# AtoD_Conversion.net
KiCad netlist of a schematic drawn in Altium Designer
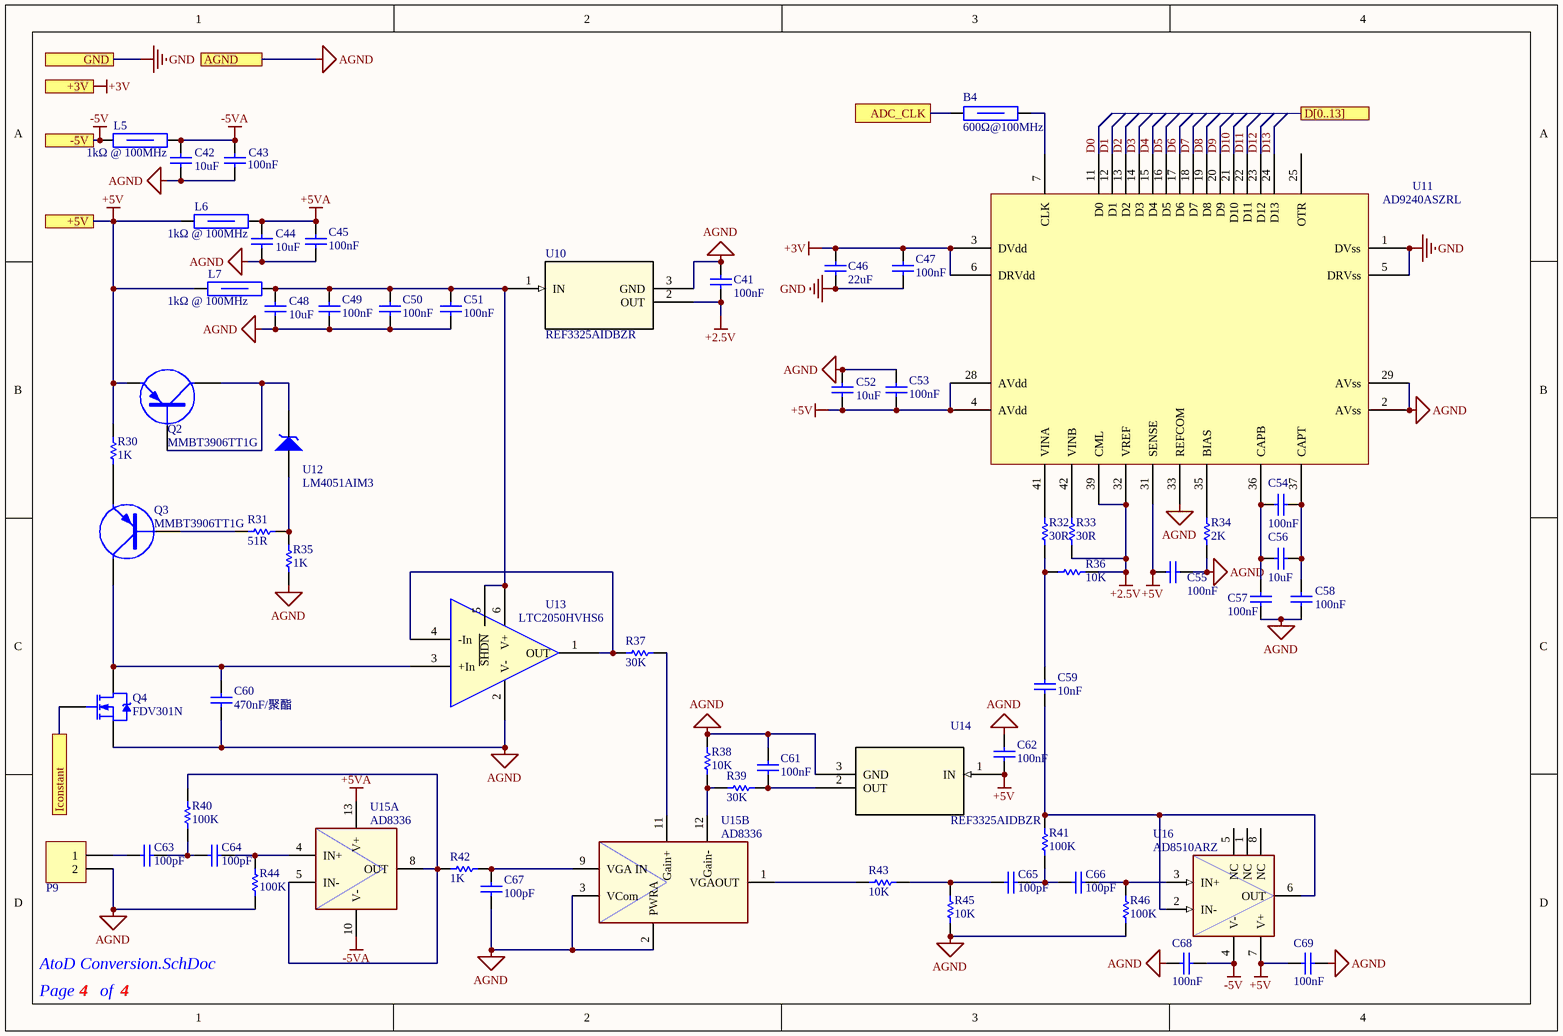
[diagram p0: AtoD Conversion.SchDoc]

(export (version "E")
  (design (tool "Eeschema 10.0.6"))
  (components
    (comp (ref "B4")
      (value "600Ω@100MHz")
      (footprint "R0805_L")
      (description "600Ω @ 100MHz \r\n线路数 1 \r\n额定电流（最大） 600mA \r\n直流电阻（DCR）（最大） 210mΩ")
      (libsource (lib "00Lib") (part "600Ω@100MHz"))
    )
    (comp (ref "C41")
      (value "100nF")
      (footprint "R0603_C")
      (description "精度 ±10% \r\n容值 100nF \r\n额定电压 50V \r\n温漂系数（介质材料) X7R")
      (libsource (lib "00Lib") (part "100nF/0603/50V"))
    )
    (comp (ref "C42")
      (value "10uF")
      (footprint "R0805_C")
      (description "精度 ±10% \r\n容值 10uF \r\n额定电压 16V \r\n温漂系数（介质材料) X7R")
      (libsource (lib "00Lib") (part "10uF/0805/16V"))
    )
    (comp (ref "C43")
      (value "100nF")
      (footprint "R0603_C")
      (description "精度 ±10% \r\n容值 100nF \r\n额定电压 50V \r\n温漂系数（介质材料) X7R")
      (libsource (lib "00Lib") (part "100nF/0603/50V"))
    )
    (comp (ref "C44")
      (value "10uF")
      (footprint "R0805_C")
      (description "精度 ±10% \r\n容值 10uF \r\n额定电压 16V \r\n温漂系数（介质材料) X7R")
      (libsource (lib "00Lib") (part "10uF/0805/16V"))
    )
    (comp (ref "C45")
      (value "100nF")
      (footprint "R0603_C")
      (description "精度 ±10% \r\n容值 100nF \r\n额定电压 50V \r\n温漂系数（介质材料) X7R")
      (libsource (lib "00Lib") (part "100nF/0603/50V"))
    )
    (comp (ref "C46")
      (value "22uF")
      (footprint "R0805_C")
      (description "精度 ±20% \r\n容值 22uF \r\n额定电压 25V \r\n温漂系数（介质材料) X5R")
      (libsource (lib "C") (part "22uF/0805/25V"))
    )
    (comp (ref "C47")
      (value "100nF")
      (footprint "R0603_C")
      (description "精度 ±10% \r\n容值 100nF \r\n额定电压 50V \r\n温漂系数（介质材料) X7R")
      (libsource (lib "00Lib") (part "100nF/0603/50V"))
    )
    (comp (ref "C48")
      (value "10uF")
      (footprint "R0805_C")
      (description "精度 ±10% \r\n容值 10uF \r\n额定电压 16V \r\n温漂系数（介质材料) X7R")
      (libsource (lib "00Lib") (part "10uF/0805/16V"))
    )
    (comp (ref "C49")
      (value "100nF")
      (footprint "R0603_C")
      (description "精度 ±10% \r\n容值 100nF \r\n额定电压 50V \r\n温漂系数（介质材料) X7R")
      (libsource (lib "00Lib") (part "100nF/0603/50V"))
    )
    (comp (ref "C50")
      (value "100nF")
      (footprint "R0603_C")
      (description "精度 ±10% \r\n容值 100nF \r\n额定电压 50V \r\n温漂系数（介质材料) X7R")
      (libsource (lib "00Lib") (part "100nF/0603/50V"))
    )
    (comp (ref "C51")
      (value "100nF")
      (footprint "R0603_C")
      (description "精度 ±10% \r\n容值 100nF \r\n额定电压 50V \r\n温漂系数（介质材料) X7R")
      (libsource (lib "00Lib") (part "100nF/0603/50V"))
    )
    (comp (ref "C52")
      (value "10uF")
      (footprint "R0805_C")
      (description "精度 ±10% \r\n容值 10uF \r\n额定电压 16V \r\n温漂系数（介质材料) X7R")
      (libsource (lib "00Lib") (part "10uF/0805/16V"))
    )
    (comp (ref "C53")
      (value "100nF")
      (footprint "R0603_C")
      (description "精度 ±10% \r\n容值 100nF \r\n额定电压 50V \r\n温漂系数（介质材料) X7R")
      (libsource (lib "00Lib") (part "100nF/0603/50V"))
    )
    (comp (ref "C54")
      (value "100nF")
      (footprint "R0603_C")
      (description "精度 ±10% \r\n容值 100nF \r\n额定电压 50V \r\n温漂系数（介质材料) X7R")
      (libsource (lib "00Lib") (part "100nF/0603/50V"))
    )
    (comp (ref "C55")
      (value "100nF")
      (footprint "R0603_C")
      (description "精度 ±10% \r\n容值 100nF \r\n额定电压 50V \r\n温漂系数（介质材料) X7R")
      (libsource (lib "00Lib") (part "100nF/0603/50V"))
    )
    (comp (ref "C56")
      (value "10uF")
      (footprint "R0805_C")
      (description "精度 ±10% \r\n容值 10uF \r\n额定电压 16V \r\n温漂系数（介质材料) X7R")
      (libsource (lib "00Lib") (part "10uF/0805/16V"))
    )
    (comp (ref "C57")
      (value "100nF")
      (footprint "R0603_C")
      (description "精度 ±10% \r\n容值 100nF \r\n额定电压 50V \r\n温漂系数（介质材料) X7R")
      (libsource (lib "00Lib") (part "100nF/0603/50V"))
    )
    (comp (ref "C58")
      (value "100nF")
      (footprint "R0603_C")
      (description "精度 ±10% \r\n容值 100nF \r\n额定电压 50V \r\n温漂系数（介质材料) X7R")
      (libsource (lib "00Lib") (part "100nF/0603/50V"))
    )
    (comp (ref "C59")
      (value "10nF")
      (footprint "R0603_C")
      (description "精度 ±5% \r\n容值 10nF \r\n额定电压 50V \r\n温漂系数（介质材料) C0G")
      (libsource (lib "00Lib") (part "10nF/0603/C0G/50V"))
    )
    (comp (ref "C60")
      (value "470nF/聚酯")
      (footprint "P=10MM -L")
      (description "聚酯薄膜电容 \r\n脚间距（mm） 10 \r\n精度 ±5% \r\n容值 470nF \r\n额定直流耐压DC 450V \r\n工作温度 -55℃ ~ +105℃")
      (libsource (lib "00Lib") (part "470nF/10mm/450V"))
    )
    (comp (ref "C61")
      (value "100nF")
      (footprint "R0603_C")
      (description "精度 ±10% \r\n容值 100nF \r\n额定电压 50V \r\n温漂系数（介质材料) X7R")
      (libsource (lib "00Lib") (part "100nF/0603/50V"))
    )
    (comp (ref "C62")
      (value "100nF")
      (footprint "R0603_C")
      (description "精度 ±10% \r\n容值 100nF \r\n额定电压 50V \r\n温漂系数（介质材料) X7R")
      (libsource (lib "00Lib") (part "100nF/0603/50V"))
    )
    (comp (ref "C63")
      (value "100pF")
      (footprint "R0603_C")
      (description "精度 ±5% \r\n容值 100pF \r\n额定电压 50V \r\n温漂系数（介质材料) C0G")
      (libsource (lib "00Lib") (part "100pF/0603/50V"))
    )
    (comp (ref "C64")
      (value "100pF")
      (footprint "R0603_C")
      (description "精度 ±5% \r\n容值 100pF \r\n额定电压 50V \r\n温漂系数（介质材料) C0G")
      (libsource (lib "00Lib") (part "100pF/0603/50V"))
    )
    (comp (ref "C65")
      (value "100pF")
      (footprint "R0603_C")
      (description "精度 ±5% \r\n容值 100pF \r\n额定电压 50V \r\n温漂系数（介质材料) C0G")
      (libsource (lib "00Lib") (part "100pF/0603/50V"))
    )
    (comp (ref "C66")
      (value "100pF")
      (footprint "R0603_C")
      (description "精度 ±5% \r\n容值 100pF \r\n额定电压 50V \r\n温漂系数（介质材料) C0G")
      (libsource (lib "00Lib") (part "100pF/0603/50V"))
    )
    (comp (ref "C67")
      (value "100pF")
      (footprint "R0603_C")
      (description "精度 ±5% \r\n容值 100pF \r\n额定电压 50V \r\n温漂系数（介质材料) C0G")
      (libsource (lib "00Lib") (part "100pF/0603/50V"))
    )
    (comp (ref "C68")
      (value "100nF")
      (footprint "R0603_C")
      (description "精度 ±10% \r\n容值 100nF \r\n额定电压 50V \r\n温漂系数（介质材料) X7R")
      (libsource (lib "00Lib") (part "100nF/0603/50V"))
    )
    (comp (ref "C69")
      (value "100nF")
      (footprint "R0603_C")
      (description "精度 ±10% \r\n容值 100nF \r\n额定电压 50V \r\n温漂系数（介质材料) X7R")
      (libsource (lib "00Lib") (part "100nF/0603/50V"))
    )
    (comp (ref "L5")
      (value "1kΩ @ 100MHz")
      (footprint "R1206_L")
      (description "阻抗 @ 频率 1kΩ @ 100MHz \r\n线路数 1 \r\n额定电流（最大） 2A \r\n直流电阻（DCR）（最大） 120mΩ")
      (libsource (lib "00Lib") (part "1kΩ@100MHz"))
    )
    (comp (ref "L6")
      (value "1kΩ @ 100MHz")
      (footprint "R1206_L")
      (description "阻抗 @ 频率 1kΩ @ 100MHz \r\n线路数 1 \r\n额定电流（最大） 2A \r\n直流电阻（DCR）（最大） 120mΩ")
      (libsource (lib "00Lib") (part "1kΩ@100MHz"))
    )
    (comp (ref "L7")
      (value "1kΩ @ 100MHz")
      (footprint "R1206_L")
      (description "阻抗 @ 频率 1kΩ @ 100MHz \r\n线路数 1 \r\n额定电流（最大） 2A \r\n直流电阻（DCR）（最大） 120mΩ")
      (libsource (lib "00Lib") (part "1kΩ@100MHz"))
    )
    (comp (ref "P9")
      (value "Header 2")
      (footprint "CP1X2")
      (description "Header, 2-Pin")
      (libsource (lib "00Lib") (part "Header 2"))
    )
    (comp (ref "Q2")
      (value "MMBT3906TT1G")
      (footprint "SOT-23(SOT-23-3)")
      (description "额定功率 200mW \r\n集电极电流Ic 200mA \r\n集射极击穿电压Vce 40V \r\n晶体管类型 PNP")
      (libsource (lib "00Lib") (part "MMBT3906TT1G"))
    )
    (comp (ref "Q3")
      (value "MMBT3906TT1G")
      (footprint "SOT-23(SOT-23-3)")
      (description "额定功率 200mW \r\n集电极电流Ic 200mA \r\n集射极击穿电压Vce 40V \r\n晶体管类型 PNP")
      (libsource (lib "00Lib") (part "MMBT3906TT1G"))
    )
    (comp (ref "Q4") (value "FDV301N") (footprint "SOT-23") (libsource (lib "00Lib") (part "FDV301N")))
    (comp (ref "R30")
      (value "1K")
      (footprint "R0603_R")
      (description "精度 ±1% \r\n温度系数 ±100ppm/℃ \r\n阻值 1kΩ \r\n功率 0.1W")
      (libsource (lib "00Lib") (part "1K/0603"))
    )
    (comp (ref "R31")
      (value "51R")
      (footprint "R0603_R")
      (description "精度 ±1% \r\n温度系数 ±100ppm/℃ \r\n功率 0.1W \r\n阻值 51Ω")
      (libsource (lib "00Lib") (part "51R/0603"))
    )
    (comp (ref "R32")
      (value "30R")
      (footprint "R0603_R")
      (description "精度 ±1% \r\n阻值 30Ω \r\n温度系数 ±100ppm/℃ \r\n功率 0.1W")
      (libsource (lib "00Lib") (part "30R/0603"))
    )
    (comp (ref "R33")
      (value "30R")
      (footprint "R0603_R")
      (description "精度 ±1% \r\n阻值 30Ω \r\n温度系数 ±100ppm/℃ \r\n功率 0.1W")
      (libsource (lib "00Lib") (part "30R/0603"))
    )
    (comp (ref "R34")
      (value "2K")
      (footprint "R0603_R")
      (description "精度 ±1% \r\n阻值 2kΩ \r\n温度系数 ±100ppm/℃ \r\n功率 0.1W")
      (libsource (lib "00Lib") (part "2K/0603"))
    )
    (comp (ref "R35")
      (value "1K")
      (footprint "R0603_R")
      (description "精度 ±1% \r\n温度系数 ±100ppm/℃ \r\n阻值 1kΩ \r\n功率 0.1W")
      (libsource (lib "00Lib") (part "1K/0603"))
    )
    (comp (ref "R36")
      (value "10K")
      (footprint "R0603_R")
      (description "精度 ±1% \r\n温度系数 ±100ppm/℃ \r\n阻值 10kΩ \r\n功率 0.1W")
      (libsource (lib "00Lib") (part "10K/0603"))
    )
    (comp (ref "R37")
      (value "30K")
      (footprint "R0603_R")
      (description "精度 ±1% \r\n阻值 30kΩ \r\n温度系数 ±100ppm/℃ \r\n功率 0.1W")
      (libsource (lib "00Lib") (part "30K/0603"))
    )
    (comp (ref "R38")
      (value "10K")
      (footprint "R0603_R")
      (description "精度 ±1% \r\n温度系数 ±100ppm/℃ \r\n阻值 10kΩ \r\n功率 0.1W")
      (libsource (lib "00Lib") (part "10K/0603"))
    )
    (comp (ref "R39")
      (value "30K")
      (footprint "R0603_R")
      (description "精度 ±1% \r\n阻值 30kΩ \r\n温度系数 ±100ppm/℃ \r\n功率 0.1W")
      (libsource (lib "00Lib") (part "30K/0603"))
    )
    (comp (ref "R40")
      (value "100K")
      (footprint "R0603_R")
      (description "精度 ±1% \r\n阻值 100kΩ \r\n温度系数 ±100ppm/℃ \r\n功率 0.1W")
      (libsource (lib "00Lib") (part "100K/0603"))
    )
    (comp (ref "R41")
      (value "100K")
      (footprint "R0603_R")
      (description "精度 ±1% \r\n阻值 100kΩ \r\n温度系数 ±100ppm/℃ \r\n功率 0.1W")
      (libsource (lib "00Lib") (part "100K/0603"))
    )
    (comp (ref "R42")
      (value "1K")
      (footprint "R0603_R")
      (description "精度 ±1% \r\n温度系数 ±100ppm/℃ \r\n阻值 1kΩ \r\n功率 0.1W")
      (libsource (lib "00Lib") (part "1K/0603"))
    )
    (comp (ref "R43")
      (value "10K")
      (footprint "R0603_R")
      (description "精度 ±1% \r\n温度系数 ±100ppm/℃ \r\n阻值 10kΩ \r\n功率 0.1W")
      (libsource (lib "00Lib") (part "10K/0603"))
    )
    (comp (ref "R44")
      (value "100K")
      (footprint "R0603_R")
      (description "精度 ±1% \r\n阻值 100kΩ \r\n温度系数 ±100ppm/℃ \r\n功率 0.1W")
      (libsource (lib "00Lib") (part "100K/0603"))
    )
    (comp (ref "R45")
      (value "10K")
      (footprint "R0603_R")
      (description "精度 ±1% \r\n温度系数 ±100ppm/℃ \r\n阻值 10kΩ \r\n功率 0.1W")
      (libsource (lib "00Lib") (part "10K/0603"))
    )
    (comp (ref "R46")
      (value "100K")
      (footprint "R0603_R")
      (description "精度 ±1% \r\n阻值 100kΩ \r\n温度系数 ±100ppm/℃ \r\n功率 0.1W")
      (libsource (lib "00Lib") (part "100K/0603"))
    )
    (comp (ref "U10")
      (value "REF3325AIDBZR")
      (footprint "SOT-23(SOT-23-3)")
      (libsource (lib "00Lib") (part "REF3325AIDBZR"))
    )
    (comp (ref "U11")
      (value "AD9240ASZRL")
      (footprint "MQFP44")
      (libsource (lib "00Lib") (part "AD9240ASZRL"))
    )
    (comp (ref "U12")
      (value "LM4051AIM3")
      (footprint "SOT-23(SOT-23-3)")
      (libsource (lib "00Lib") (part "LM4051AIM3-ADJ/NOPB"))
    )
    (comp (ref "U13")
      (value "LTC2050HVHS6")
      (footprint "DBV0006A_N")
      (libsource (lib "00Lib") (part "LTC2050HVHS6"))
    )
    (comp (ref "U14")
      (value "REF3325AIDBZR")
      (footprint "SOT-23(SOT-23-3)")
      (libsource (lib "") (part "REF3325AIDBZR_1"))
    )
    (comp (ref "U15") (value "AD8336") (footprint "LFCSP16") (libsource (lib "00Lib") (part "AD8336ACPZ WP")))
    (comp (ref "U16")
      (value "AD8510ARZ")
      (footprint "SOP-8_150mil")
      (libsource (lib "00Lib") (part "AD8510ARZ"))
    )
  )
  (nets
    (net (code "1") (name "+2.5V") (class "Default")
      (node (ref "C41") (pin "2") (pinfunction "2_2") (pintype "passive"))
      (node (ref "R33") (pin "1") (pinfunction "1_1") (pintype "passive"))
      (node (ref "R36") (pin "1") (pinfunction "1_1") (pintype "passive"))
      (node (ref "U10") (pin "2") (pinfunction "OUT_2") (pintype "power_in"))
      (node (ref "U11") (pin "32") (pinfunction "VREF_32") (pintype "passive"))
      (node (ref "U11") (pin "39") (pinfunction "CML_39") (pintype "passive"))
    )
    (net (code "2") (name "+3V") (class "Default")
      (node (ref "C46") (pin "2") (pinfunction "2_2") (pintype "passive"))
      (node (ref "C47") (pin "2") (pinfunction "2_2") (pintype "passive"))
      (node (ref "U11") (pin "3") (pinfunction "DVdd_3") (pintype "passive"))
      (node (ref "U11") (pin "6") (pinfunction "DRVdd_6") (pintype "passive"))
    )
    (net (code "3") (name "+5V") (class "Default")
      (node (ref "C52") (pin "1") (pinfunction "1_1") (pintype "passive"))
      (node (ref "C53") (pin "1") (pinfunction "1_1") (pintype "passive"))
      (node (ref "C55") (pin "2") (pinfunction "2_2") (pintype "passive"))
      (node (ref "C62") (pin "1") (pinfunction "1_1") (pintype "passive"))
      (node (ref "C69") (pin "2") (pinfunction "2_2") (pintype "passive"))
      (node (ref "L6") (pin "1") (pinfunction "1_1") (pintype "passive"))
      (node (ref "L7") (pin "1") (pinfunction "1_1") (pintype "passive"))
      (node (ref "Q2") (pin "2") (pinfunction "E_2") (pintype "passive"))
      (node (ref "R30") (pin "2") (pinfunction "2_2") (pintype "passive"))
      (node (ref "U11") (pin "28") (pinfunction "AVdd_28") (pintype "passive"))
      (node (ref "U11") (pin "31") (pinfunction "SENSE_31") (pintype "passive"))
      (node (ref "U11") (pin "4") (pinfunction "AVdd_4") (pintype "passive"))
      (node (ref "U14") (pin "1") (pinfunction "IN_1") (pintype "input"))
      (node (ref "U16") (pin "7") (pinfunction "V+_7") (pintype "passive"))
    )
    (net (code "4") (name "+5VA") (class "Default")
      (node (ref "C44") (pin "2") (pinfunction "2_2") (pintype "passive"))
      (node (ref "C45") (pin "2") (pinfunction "2_2") (pintype "passive"))
      (node (ref "L6") (pin "2") (pinfunction "2_2") (pintype "passive"))
      (node (ref "U15") (pin "13") (pinfunction "V+_13") (pintype "passive"))
    )
    (net (code "5") (name "-5V") (class "Default")
      (node (ref "C68") (pin "1") (pinfunction "1_1") (pintype "passive"))
      (node (ref "L5") (pin "1") (pinfunction "1_1") (pintype "passive"))
      (node (ref "U16") (pin "4") (pinfunction "V-_4") (pintype "power_in"))
    )
    (net (code "6") (name "-5VA") (class "Default")
      (node (ref "C42") (pin "2") (pinfunction "2_2") (pintype "passive"))
      (node (ref "C43") (pin "2") (pinfunction "2_2") (pintype "passive"))
      (node (ref "L5") (pin "2") (pinfunction "2_2") (pintype "passive"))
      (node (ref "U15") (pin "10") (pinfunction "V-_10") (pintype "passive"))
    )
    (net (code "7") (name "/ADC_CLK") (class "Default")
      (node (ref "B4") (pin "1") (pinfunction "1_1") (pintype "passive"))
    )
    (net (code "8") (name "/D0") (class "Default")
      (node (ref "U11") (pin "11") (pinfunction "D0_11") (pintype "passive"))
    )
    (net (code "9") (name "/D1") (class "Default")
      (node (ref "U11") (pin "12") (pinfunction "D1_12") (pintype "passive"))
    )
    (net (code "10") (name "/D2") (class "Default")
      (node (ref "U11") (pin "13") (pinfunction "D2_13") (pintype "passive"))
    )
    (net (code "11") (name "/D3") (class "Default")
      (node (ref "U11") (pin "14") (pinfunction "D3_14") (pintype "passive"))
    )
    (net (code "12") (name "/D4") (class "Default")
      (node (ref "U11") (pin "15") (pinfunction "D4_15") (pintype "passive"))
    )
    (net (code "13") (name "/D5") (class "Default")
      (node (ref "U11") (pin "16") (pinfunction "D5_16") (pintype "passive"))
    )
    (net (code "14") (name "/D6") (class "Default")
      (node (ref "U11") (pin "17") (pinfunction "D6_17") (pintype "passive"))
    )
    (net (code "15") (name "/D7") (class "Default")
      (node (ref "U11") (pin "18") (pinfunction "D7_18") (pintype "passive"))
    )
    (net (code "16") (name "/D8") (class "Default")
      (node (ref "U11") (pin "19") (pinfunction "D8_19") (pintype "passive"))
    )
    (net (code "17") (name "/D9") (class "Default")
      (node (ref "U11") (pin "20") (pinfunction "D9_20") (pintype "passive"))
    )
    (net (code "18") (name "/D10") (class "Default")
      (node (ref "U11") (pin "21") (pinfunction "D10_21") (pintype "passive"))
    )
    (net (code "19") (name "/D11") (class "Default")
      (node (ref "U11") (pin "22") (pinfunction "D11_22") (pintype "passive"))
    )
    (net (code "20") (name "/D12") (class "Default")
      (node (ref "U11") (pin "23") (pinfunction "D12_23") (pintype "passive"))
    )
    (net (code "21") (name "/D13") (class "Default")
      (node (ref "U11") (pin "24") (pinfunction "D13_24") (pintype "passive"))
    )
    (net (code "23") (name "/Iconstant") (class "Default")
      (node (ref "Q4") (pin "1") (pinfunction "G_1") (pintype "passive"))
    )
    (net (code "24") (name "AGND") (class "Default")
      (node (ref "C41") (pin "1") (pinfunction "1_1") (pintype "passive"))
      (node (ref "C42") (pin "1") (pinfunction "1_1") (pintype "passive"))
      (node (ref "C43") (pin "1") (pinfunction "1_1") (pintype "passive"))
      (node (ref "C44") (pin "1") (pinfunction "1_1") (pintype "passive"))
      (node (ref "C45") (pin "1") (pinfunction "1_1") (pintype "passive"))
      (node (ref "C48") (pin "1") (pinfunction "1_1") (pintype "passive"))
      (node (ref "C49") (pin "1") (pinfunction "1_1") (pintype "passive"))
      (node (ref "C50") (pin "1") (pinfunction "1_1") (pintype "passive"))
      (node (ref "C51") (pin "1") (pinfunction "1_1") (pintype "passive"))
      (node (ref "C52") (pin "2") (pinfunction "2_2") (pintype "passive"))
      (node (ref "C53") (pin "2") (pinfunction "2_2") (pintype "passive"))
      (node (ref "C55") (pin "1") (pinfunction "1_1") (pintype "passive"))
      (node (ref "C57") (pin "2") (pinfunction "2_2") (pintype "passive"))
      (node (ref "C58") (pin "2") (pinfunction "2_2") (pintype "passive"))
      (node (ref "C60") (pin "1") (pinfunction "1_1") (pintype "passive"))
      (node (ref "C61") (pin "2") (pinfunction "2_2") (pintype "passive"))
      (node (ref "C62") (pin "2") (pinfunction "2_2") (pintype "passive"))
      (node (ref "C67") (pin "1") (pinfunction "1_1") (pintype "passive"))
      (node (ref "C68") (pin "2") (pinfunction "2_2") (pintype "passive"))
      (node (ref "C69") (pin "1") (pinfunction "1_1") (pintype "passive"))
      (node (ref "P9") (pin "2") (pinfunction "2_2") (pintype "passive"))
      (node (ref "Q4") (pin "2") (pinfunction "S_2") (pintype "passive"))
      (node (ref "R34") (pin "1") (pinfunction "1_1") (pintype "passive"))
      (node (ref "R35") (pin "1") (pinfunction "1_1") (pintype "passive"))
      (node (ref "R38") (pin "2") (pinfunction "2_2") (pintype "passive"))
      (node (ref "R44") (pin "2") (pinfunction "2_2") (pintype "passive"))
      (node (ref "R45") (pin "1") (pinfunction "1_1") (pintype "passive"))
      (node (ref "R46") (pin "2") (pinfunction "2_2") (pintype "passive"))
      (node (ref "U10") (pin "3") (pinfunction "GND_3") (pintype "power_in"))
      (node (ref "U11") (pin "2") (pinfunction "AVss_2") (pintype "passive"))
      (node (ref "U11") (pin "29") (pinfunction "AVss_29") (pintype "passive"))
      (node (ref "U11") (pin "33") (pinfunction "REFCOM_33") (pintype "passive"))
      (node (ref "U13") (pin "2") (pinfunction "V-_2") (pintype "passive"))
      (node (ref "U14") (pin "3") (pinfunction "GND_3") (pintype "power_in"))
      (node (ref "U15") (pin "2") (pinfunction "PWRA_2") (pintype "passive"))
      (node (ref "U15") (pin "3") (pinfunction "VCom_3") (pintype "passive"))
    )
    (net (code "25") (name "GND") (class "Default")
      (node (ref "C46") (pin "1") (pinfunction "1_1") (pintype "passive"))
      (node (ref "C47") (pin "1") (pinfunction "1_1") (pintype "passive"))
      (node (ref "U11") (pin "1") (pinfunction "DVss_1") (pintype "passive"))
      (node (ref "U11") (pin "5") (pinfunction "DRVss_5") (pintype "passive"))
    )
    (net (code "26") (name "Net-(C59-Pad2)") (class "Default")
      (node (ref "C59") (pin "2") (pinfunction "2_2") (pintype "passive"))
      (node (ref "R32") (pin "1") (pinfunction "1_1") (pintype "passive"))
      (node (ref "R36") (pin "2") (pinfunction "2_2") (pintype "passive"))
    )
    (net (code "27") (name "Net-(C63-Pad1)") (class "Default")
      (node (ref "C63") (pin "1") (pinfunction "1_1") (pintype "passive"))
      (node (ref "P9") (pin "1") (pinfunction "1_1") (pintype "passive"))
    )
    (net (code "28") (name "Net-(C63-Pad2)") (class "Default")
      (node (ref "C63") (pin "2") (pinfunction "2_2") (pintype "passive"))
      (node (ref "C64") (pin "1") (pinfunction "1_1") (pintype "passive"))
      (node (ref "R40") (pin "2") (pinfunction "2_2") (pintype "passive"))
    )
    (net (code "29") (name "Net-(C65-Pad1)") (class "Default")
      (node (ref "C65") (pin "1") (pinfunction "1_1") (pintype "passive"))
      (node (ref "R43") (pin "1") (pinfunction "1_1") (pintype "passive"))
      (node (ref "R45") (pin "2") (pinfunction "2_2") (pintype "passive"))
    )
    (net (code "30") (name "Net-(C65-Pad2)") (class "Default")
      (node (ref "C65") (pin "2") (pinfunction "2_2") (pintype "passive"))
      (node (ref "C66") (pin "1") (pinfunction "1_1") (pintype "passive"))
      (node (ref "R41") (pin "2") (pinfunction "2_2") (pintype "passive"))
    )
    (net (code "31") (name "Net-(Q2-B)") (class "Default")
      (node (ref "Q2") (pin "1") (pinfunction "B_1") (pintype "passive"))
      (node (ref "Q2") (pin "3") (pinfunction "C_3") (pintype "passive"))
      (node (ref "U12") (pin "1") (pintype "passive"))
    )
    (net (code "32") (name "Net-(Q3-B)") (class "Default")
      (node (ref "Q3") (pin "1") (pinfunction "B_1") (pintype "passive"))
      (node (ref "R31") (pin "1") (pinfunction "1_1") (pintype "passive"))
    )
    (net (code "33") (name "Net-(Q3-C)") (class "Default")
      (node (ref "C60") (pin "2") (pinfunction "2_2") (pintype "passive"))
      (node (ref "Q3") (pin "3") (pinfunction "C_3") (pintype "passive"))
      (node (ref "Q4") (pin "3") (pinfunction "D_3") (pintype "passive"))
      (node (ref "U13") (pin "3") (pinfunction "+In_3") (pintype "passive"))
    )
    (net (code "34") (name "Net-(Q3-E)") (class "Default")
      (node (ref "Q3") (pin "2") (pinfunction "E_2") (pintype "passive"))
      (node (ref "R30") (pin "1") (pinfunction "1_1") (pintype "passive"))
    )
    (net (code "35") (name "Net-(R31-Pad2)") (class "Default")
      (node (ref "R31") (pin "2") (pinfunction "2_2") (pintype "passive"))
      (node (ref "R35") (pin "2") (pinfunction "2_2") (pintype "passive"))
      (node (ref "U12") (pin "2") (pintype "passive"))
    )
    (net (code "36") (name "Net-(U10-IN)") (class "Default")
      (node (ref "C48") (pin "2") (pinfunction "2_2") (pintype "passive"))
      (node (ref "C49") (pin "2") (pinfunction "2_2") (pintype "passive"))
      (node (ref "C50") (pin "2") (pinfunction "2_2") (pintype "passive"))
      (node (ref "C51") (pin "2") (pinfunction "2_2") (pintype "passive"))
      (node (ref "L7") (pin "2") (pinfunction "2_2") (pintype "passive"))
      (node (ref "U10") (pin "1") (pinfunction "IN_1") (pintype "input"))
      (node (ref "U13") (pin "5") (pinfunction "~{SHDN}_5") (pintype "passive"))
      (node (ref "U13") (pin "6") (pinfunction "V+_6") (pintype "passive"))
    )
    (net (code "37") (name "Net-(U11-BIAS)") (class "Default")
      (node (ref "R34") (pin "2") (pinfunction "2_2") (pintype "passive"))
      (node (ref "U11") (pin "35") (pinfunction "BIAS_35") (pintype "passive"))
    )
    (net (code "38") (name "Net-(U11-CAPB)") (class "Default")
      (node (ref "C54") (pin "2") (pinfunction "2_2") (pintype "passive"))
      (node (ref "C56") (pin "2") (pinfunction "2_2") (pintype "passive"))
      (node (ref "C57") (pin "1") (pinfunction "1_1") (pintype "passive"))
      (node (ref "U11") (pin "36") (pinfunction "CAPB_36") (pintype "passive"))
    )
    (net (code "39") (name "Net-(U11-CAPT)") (class "Default")
      (node (ref "C54") (pin "1") (pinfunction "1_1") (pintype "passive"))
      (node (ref "C56") (pin "1") (pinfunction "1_1") (pintype "passive"))
      (node (ref "C58") (pin "1") (pinfunction "1_1") (pintype "passive"))
      (node (ref "U11") (pin "37") (pinfunction "CAPT_37") (pintype "passive"))
    )
    (net (code "40") (name "Net-(U11-CLK)") (class "Default")
      (node (ref "B4") (pin "2") (pinfunction "2_2") (pintype "passive"))
      (node (ref "U11") (pin "7") (pinfunction "CLK_7") (pintype "passive"))
    )
    (net (code "41") (name "Net-(U11-VINA)") (class "Default")
      (node (ref "R32") (pin "2") (pinfunction "2_2") (pintype "passive"))
      (node (ref "U11") (pin "41") (pinfunction "VINA_41") (pintype "passive"))
    )
    (net (code "42") (name "Net-(U11-VINB)") (class "Default")
      (node (ref "R33") (pin "2") (pinfunction "2_2") (pintype "passive"))
      (node (ref "U11") (pin "42") (pinfunction "VINB_42") (pintype "passive"))
    )
    (net (code "43") (name "Net-(U13--In)") (class "Default")
      (node (ref "R37") (pin "1") (pinfunction "1_1") (pintype "passive"))
      (node (ref "U13") (pin "1") (pinfunction "OUT_1") (pintype "passive"))
      (node (ref "U13") (pin "4") (pinfunction "-In_4") (pintype "passive"))
    )
    (net (code "44") (name "Net-(U14-OUT)") (class "Default")
      (node (ref "C61") (pin "1") (pinfunction "1_1") (pintype "passive"))
      (node (ref "R39") (pin "1") (pinfunction "1_1") (pintype "passive"))
      (node (ref "U14") (pin "2") (pinfunction "OUT_2") (pintype "power_in"))
    )
    (net (code "45") (name "Net-(U15A-IN+)") (class "Default")
      (node (ref "C64") (pin "2") (pinfunction "2_2") (pintype "passive"))
      (node (ref "R44") (pin "1") (pinfunction "1_1") (pintype "passive"))
      (node (ref "U15") (pin "4") (pinfunction "IN+_4") (pintype "passive"))
    )
    (net (code "46") (name "Net-(U15A-IN-)") (class "Default")
      (node (ref "R40") (pin "1") (pinfunction "1_1") (pintype "passive"))
      (node (ref "R42") (pin "2") (pinfunction "2_2") (pintype "passive"))
      (node (ref "U15") (pin "5") (pinfunction "IN-_5") (pintype "passive"))
      (node (ref "U15") (pin "8") (pinfunction "OUT_8") (pintype "passive"))
    )
    (net (code "47") (name "Net-(U15B-Gain+)") (class "Default")
      (node (ref "R37") (pin "2") (pinfunction "2_2") (pintype "passive"))
      (node (ref "U15") (pin "11") (pinfunction "Gain+_11") (pintype "passive"))
    )
    (net (code "48") (name "Net-(U15B-Gain-)") (class "Default")
      (node (ref "R38") (pin "1") (pinfunction "1_1") (pintype "passive"))
      (node (ref "R39") (pin "2") (pinfunction "2_2") (pintype "passive"))
      (node (ref "U15") (pin "12") (pinfunction "Gain-_12") (pintype "passive"))
    )
    (net (code "49") (name "Net-(U15B-VGAOUT)") (class "Default")
      (node (ref "R43") (pin "2") (pinfunction "2_2") (pintype "passive"))
      (node (ref "U15") (pin "1") (pinfunction "VGAOUT_1") (pintype "passive"))
    )
    (net (code "50") (name "Net-(U15B-VGA_IN)") (class "Default")
      (node (ref "C67") (pin "2") (pinfunction "2_2") (pintype "passive"))
      (node (ref "R42") (pin "1") (pinfunction "1_1") (pintype "passive"))
      (node (ref "U15") (pin "9") (pinfunction "VGA_IN_9") (pintype "passive"))
    )
    (net (code "51") (name "Net-(U16-IN+)") (class "Default")
      (node (ref "C66") (pin "2") (pinfunction "2_2") (pintype "passive"))
      (node (ref "R46") (pin "1") (pinfunction "1_1") (pintype "passive"))
      (node (ref "U16") (pin "3") (pinfunction "IN+_3") (pintype "input"))
    )
    (net (code "52") (name "Net-(U16-IN-)") (class "Default")
      (node (ref "C59") (pin "1") (pinfunction "1_1") (pintype "passive"))
      (node (ref "R41") (pin "1") (pinfunction "1_1") (pintype "passive"))
      (node (ref "U16") (pin "2") (pinfunction "IN-_2") (pintype "input"))
      (node (ref "U16") (pin "6") (pinfunction "OUT_6") (pintype "passive"))
    )
    (net (code "53") (name "unconnected-(U11-OTR-Pad25)") (class "Default")
      (node (ref "U11") (pin "25") (pinfunction "OTR_25") (pintype "passive"))
    )
    (net (code "54") (name "unconnected-(U16-NC-Pad1)") (class "Default")
      (node (ref "U16") (pin "1") (pinfunction "NC_1") (pintype "passive"))
    )
    (net (code "55") (name "unconnected-(U16-NC-Pad5)") (class "Default")
      (node (ref "U16") (pin "5") (pinfunction "NC_5") (pintype "passive"))
    )
    (net (code "56") (name "unconnected-(U16-NC-Pad8)") (class "Default")
      (node (ref "U16") (pin "8") (pinfunction "NC_8") (pintype "passive"))
    )
  )
)
